# Recepitor.net
KiCad netlist of a schematic drawn in Altium Designer
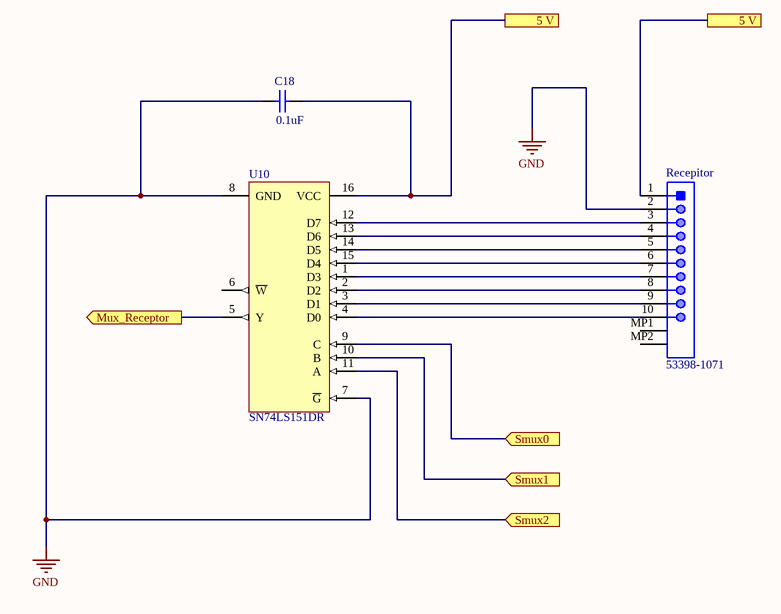
[diagram p0: Recepitor.SchDoc]

(export (version "E")
  (design (tool "Eeschema 10.0.6"))
  (components
    (comp (ref "C18")
      (value "710-885012206071")
      (footprint "CAPC1608X90X30LL10T20")
      (fields
        (field (name "VOLTAGE") "25Vdc")
        (field (name "MANUFACTURER") "SamsungElectro-Mechanics")
        (field (name "CAPACITANCE VALUE") "0.1uF")
        (field (name "TOLERANCE") "10%")
      )
      (libsource (lib "CAP 0603 100nF") (part "CMP-2000-06092-1"))
    )
    (comp (ref "Recepitor")
      (value "53398-1071")
      (footprint "MOLX-53398-1071_V")
      (description "Male Header, Pitch 1.25 mm, 1 x 10 Position, Height 4.7 mm, -40 to 85 degC, RoHS, Tape and Reel")
      (fields (field (name "MANUFACTURER") "Molex"))
      (libsource (lib "Molex_53398-1071") (part "CMP-2000-05635-1"))
    )
    (comp (ref "U10")
      (value "SN74LS151DR")
      (footprint "D0016A_L")
      (description "8-Line To 1-Line Data Selectors/Multiplexers, D0016A, LARGE T&R")
      (fields
        (field (name "MANUFACTURER") "Texas Instruments")
        (field (name "GENERIC PART NUMBER") "SN74LS151")
      )
      (libsource (lib "mux SN74LS151DR") (part "CMP-1633-00148-1"))
    )
  )
  (nets
    (net (code "1") (name "/5 V") (class "Default")
      (node (ref "C18") (pin "2") (pinfunction "2_2") (pintype "passive"))
      (node (ref "Recepitor") (pin "1") (pinfunction "1_1") (pintype "passive"))
      (node (ref "U10") (pin "16") (pinfunction "VCC_16") (pintype "power_in"))
    )
    (net (code "2") (name "/Mux_Receptor") (class "Default")
      (node (ref "U10") (pin "5") (pinfunction "Y_5") (pintype "output"))
    )
    (net (code "3") (name "/Smux0") (class "Default")
      (node (ref "U10") (pin "9") (pinfunction "C_9") (pintype "input"))
    )
    (net (code "4") (name "/Smux1") (class "Default")
      (node (ref "U10") (pin "10") (pinfunction "B_10") (pintype "input"))
    )
    (net (code "5") (name "/Smux2") (class "Default")
      (node (ref "U10") (pin "11") (pinfunction "A_11") (pintype "input"))
    )
    (net (code "6") (name "GND") (class "Default")
      (node (ref "C18") (pin "1") (pinfunction "1_1") (pintype "passive"))
      (node (ref "Recepitor") (pin "2") (pinfunction "2_2") (pintype "passive"))
      (node (ref "U10") (pin "7") (pinfunction "~{G}_7") (pintype "input"))
      (node (ref "U10") (pin "8") (pinfunction "GND_8") (pintype "power_in"))
    )
    (net (code "7") (name "Net-(U10-D0)") (class "Default")
      (node (ref "Recepitor") (pin "10") (pinfunction "10_10") (pintype "passive"))
      (node (ref "U10") (pin "4") (pinfunction "D0_4") (pintype "input"))
    )
    (net (code "8") (name "Net-(U10-D1)") (class "Default")
      (node (ref "Recepitor") (pin "9") (pinfunction "9_9") (pintype "passive"))
      (node (ref "U10") (pin "3") (pinfunction "D1_3") (pintype "input"))
    )
    (net (code "9") (name "Net-(U10-D2)") (class "Default")
      (node (ref "Recepitor") (pin "8") (pinfunction "8_8") (pintype "passive"))
      (node (ref "U10") (pin "2") (pinfunction "D2_2") (pintype "input"))
    )
    (net (code "10") (name "Net-(U10-D3)") (class "Default")
      (node (ref "Recepitor") (pin "7") (pinfunction "7_7") (pintype "passive"))
      (node (ref "U10") (pin "1") (pinfunction "D3_1") (pintype "input"))
    )
    (net (code "11") (name "Net-(U10-D4)") (class "Default")
      (node (ref "Recepitor") (pin "6") (pinfunction "6_6") (pintype "passive"))
      (node (ref "U10") (pin "15") (pinfunction "D4_15") (pintype "input"))
    )
    (net (code "12") (name "Net-(U10-D5)") (class "Default")
      (node (ref "Recepitor") (pin "5") (pinfunction "5_5") (pintype "passive"))
      (node (ref "U10") (pin "14") (pinfunction "D5_14") (pintype "input"))
    )
    (net (code "13") (name "Net-(U10-D6)") (class "Default")
      (node (ref "Recepitor") (pin "4") (pinfunction "4_4") (pintype "passive"))
      (node (ref "U10") (pin "13") (pinfunction "D6_13") (pintype "input"))
    )
    (net (code "14") (name "Net-(U10-D7)") (class "Default")
      (node (ref "Recepitor") (pin "3") (pinfunction "3_3") (pintype "passive"))
      (node (ref "U10") (pin "12") (pinfunction "D7_12") (pintype "input"))
    )
    (net (code "15") (name "unconnected-(Recepitor-PadMP1)") (class "Default")
      (node (ref "Recepitor") (pin "MP1") (pinfunction "MP1_MP1") (pintype "passive"))
    )
    (net (code "16") (name "unconnected-(Recepitor-PadMP2)") (class "Default")
      (node (ref "Recepitor") (pin "MP2") (pinfunction "MP2_MP2") (pintype "passive"))
    )
    (net (code "17") (name "unconnected-(U10-~{W}-Pad6)") (class "Default")
      (node (ref "U10") (pin "6") (pinfunction "~{W}_6") (pintype "output"))
    )
  )
)
